# Sheet1.net
KiCad netlist of a schematic drawn in Altium Designer
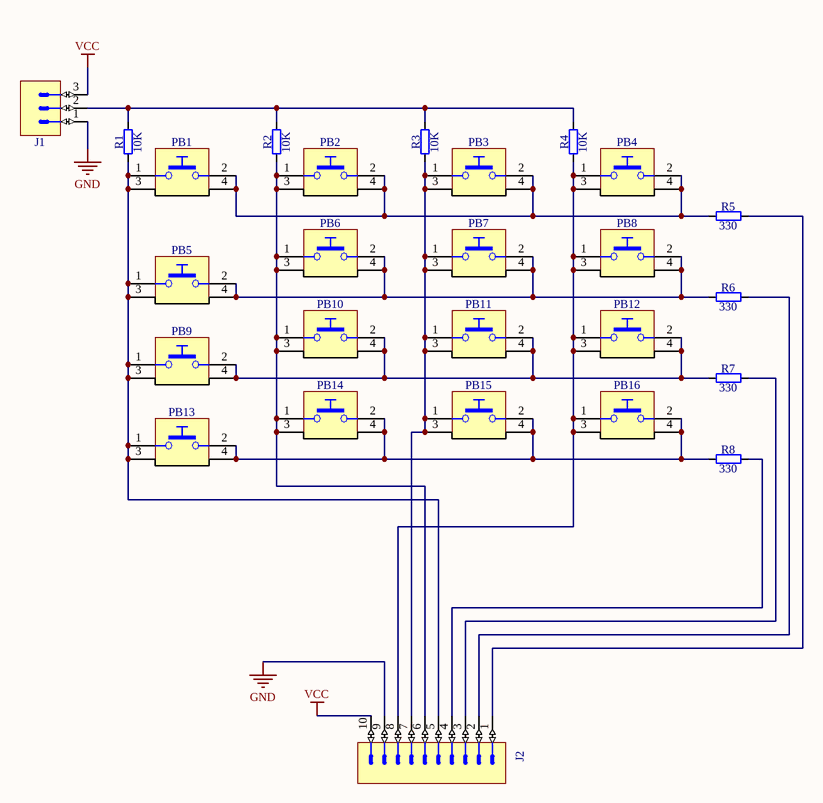
[diagram p0: Sheet1.SchDoc]

(export (version "E")
  (design (tool "Eeschema 10.0.6"))
  (components
    (comp (ref "J1")
      (value "~")
      (footprint "HARWIN_M22-2010305")
      (description "Connector 3 Male")
      (libsource (lib "Schlib1") (part "Connector 3 Male"))
    )
    (comp (ref "J2")
      (value "~")
      (footprint "SIP10")
      (description "Connector 10 Male")
      (libsource (lib "Schlib1") (part "Connector 10 Male"))
    )
    (comp (ref "PB1")
      (value "~")
      (footprint "PB_TYCO_FSM6JSMA")
      (description "Push-Button Switch SPDT")
      (libsource (lib "Schlib1") (part "PB SPST 1NO-2NO 34CASE"))
    )
    (comp (ref "PB2")
      (value "~")
      (footprint "PB_TYCO_FSM6JSMA")
      (description "Push-Button Switch SPDT")
      (libsource (lib "Schlib1") (part "PB SPST 1NO-2NO 34CASE"))
    )
    (comp (ref "PB3")
      (value "~")
      (footprint "PB_TYCO_FSM6JSMA")
      (description "Push-Button Switch SPDT")
      (libsource (lib "Schlib1") (part "PB SPST 1NO-2NO 34CASE"))
    )
    (comp (ref "PB4")
      (value "~")
      (footprint "PB_TYCO_FSM6JSMA")
      (description "Push-Button Switch SPDT")
      (libsource (lib "Schlib1") (part "PB SPST 1NO-2NO 34CASE"))
    )
    (comp (ref "PB5")
      (value "~")
      (footprint "PB_TYCO_FSM6JSMA")
      (description "Push-Button Switch SPDT")
      (libsource (lib "Schlib1") (part "PB SPST 1NO-2NO 34CASE"))
    )
    (comp (ref "PB6")
      (value "~")
      (footprint "PB_TYCO_FSM6JSMA")
      (description "Push-Button Switch SPDT")
      (libsource (lib "Schlib1") (part "PB SPST 1NO-2NO 34CASE"))
    )
    (comp (ref "PB7")
      (value "~")
      (footprint "PB_TYCO_FSM6JSMA")
      (description "Push-Button Switch SPDT")
      (libsource (lib "Schlib1") (part "PB SPST 1NO-2NO 34CASE"))
    )
    (comp (ref "PB8")
      (value "~")
      (footprint "PB_TYCO_FSM6JSMA")
      (description "Push-Button Switch SPDT")
      (libsource (lib "Schlib1") (part "PB SPST 1NO-2NO 34CASE"))
    )
    (comp (ref "PB9")
      (value "~")
      (footprint "PB_TYCO_FSM6JSMA")
      (description "Push-Button Switch SPDT")
      (libsource (lib "Schlib1") (part "PB SPST 1NO-2NO 34CASE"))
    )
    (comp (ref "PB10")
      (value "~")
      (footprint "PB_TYCO_FSM6JSMA")
      (description "Push-Button Switch SPDT")
      (libsource (lib "Schlib1") (part "PB SPST 1NO-2NO 34CASE"))
    )
    (comp (ref "PB11")
      (value "~")
      (footprint "PB_TYCO_FSM6JSMA")
      (description "Push-Button Switch SPDT")
      (libsource (lib "Schlib1") (part "PB SPST 1NO-2NO 34CASE"))
    )
    (comp (ref "PB12")
      (value "~")
      (footprint "PB_TYCO_FSM6JSMA")
      (description "Push-Button Switch SPDT")
      (libsource (lib "Schlib1") (part "PB SPST 1NO-2NO 34CASE"))
    )
    (comp (ref "PB13")
      (value "~")
      (footprint "PB_TYCO_FSM6JSMA")
      (description "Push-Button Switch SPDT")
      (libsource (lib "Schlib1") (part "PB SPST 1NO-2NO 34CASE"))
    )
    (comp (ref "PB14")
      (value "~")
      (footprint "PB_TYCO_FSM6JSMA")
      (description "Push-Button Switch SPDT")
      (libsource (lib "Schlib1") (part "PB SPST 1NO-2NO 34CASE"))
    )
    (comp (ref "PB15")
      (value "~")
      (footprint "PB_TYCO_FSM6JSMA")
      (description "Push-Button Switch SPDT")
      (libsource (lib "Schlib1") (part "PB SPST 1NO-2NO 34CASE"))
    )
    (comp (ref "PB16")
      (value "~")
      (footprint "PB_TYCO_FSM6JSMA")
      (description "Push-Button Switch SPDT")
      (libsource (lib "Schlib1") (part "PB SPST 1NO-2NO 34CASE"))
    )
    (comp (ref "R1")
      (value "10K")
      (footprint "RESC2012X60N")
      (description "Resistor")
      (libsource (lib "Schlib1") (part "Resistor"))
    )
    (comp (ref "R2")
      (value "10K")
      (footprint "RESC2012X60N")
      (description "Resistor")
      (libsource (lib "Schlib1") (part "Resistor"))
    )
    (comp (ref "R3")
      (value "10K")
      (footprint "RESC2012X60N")
      (description "Resistor")
      (libsource (lib "Schlib1") (part "Resistor"))
    )
    (comp (ref "R4")
      (value "10K")
      (footprint "RESC2012X60N")
      (description "Resistor")
      (libsource (lib "Schlib1") (part "Resistor"))
    )
    (comp (ref "R5")
      (value "330")
      (footprint "RESC2012X60N")
      (description "Resistor")
      (libsource (lib "Schlib1") (part "Resistor"))
    )
    (comp (ref "R6")
      (value "330")
      (footprint "RESC2012X60N")
      (description "Resistor")
      (libsource (lib "Schlib1") (part "Resistor"))
    )
    (comp (ref "R7")
      (value "330")
      (footprint "RESC2012X60N")
      (description "Resistor")
      (libsource (lib "Schlib1") (part "Resistor"))
    )
    (comp (ref "R8")
      (value "330")
      (footprint "RESC2012X60N")
      (description "Resistor")
      (libsource (lib "Schlib1") (part "Resistor"))
    )
  )
  (nets
    (net (code "1") (name "GND") (class "Default")
      (node (ref "J1") (pin "1") (pinfunction "1_1") (pintype "bidirectional"))
      (node (ref "J2") (pin "9") (pinfunction "9_9") (pintype "bidirectional"))
    )
    (net (code "2") (name "Net-(J1-Pad2)") (class "Default")
      (node (ref "J1") (pin "2") (pinfunction "2_2") (pintype "bidirectional"))
      (node (ref "R1") (pin "2") (pinfunction "2_2") (pintype "passive"))
      (node (ref "R2") (pin "2") (pinfunction "2_2") (pintype "passive"))
      (node (ref "R3") (pin "2") (pinfunction "2_2") (pintype "passive"))
      (node (ref "R4") (pin "2") (pinfunction "2_2") (pintype "passive"))
    )
    (net (code "3") (name "Net-(J2-Pad1)") (class "Default")
      (node (ref "J2") (pin "1") (pinfunction "1_1") (pintype "bidirectional"))
      (node (ref "R5") (pin "2") (pinfunction "2_2") (pintype "passive"))
    )
    (net (code "4") (name "Net-(J2-Pad2)") (class "Default")
      (node (ref "J2") (pin "2") (pinfunction "2_2") (pintype "bidirectional"))
      (node (ref "R6") (pin "2") (pinfunction "2_2") (pintype "passive"))
    )
    (net (code "5") (name "Net-(J2-Pad3)") (class "Default")
      (node (ref "J2") (pin "3") (pinfunction "3_3") (pintype "bidirectional"))
      (node (ref "R7") (pin "2") (pinfunction "2_2") (pintype "passive"))
    )
    (net (code "6") (name "Net-(J2-Pad4)") (class "Default")
      (node (ref "J2") (pin "4") (pinfunction "4_4") (pintype "bidirectional"))
      (node (ref "R8") (pin "2") (pinfunction "2_2") (pintype "passive"))
    )
    (net (code "7") (name "Net-(J2-Pad5)") (class "Default")
      (node (ref "J2") (pin "5") (pinfunction "5_5") (pintype "bidirectional"))
      (node (ref "PB1") (pin "1") (pinfunction "1_1") (pintype "passive"))
      (node (ref "PB1") (pin "3") (pinfunction "3_3") (pintype "passive"))
      (node (ref "PB13") (pin "1") (pinfunction "1_1") (pintype "passive"))
      (node (ref "PB13") (pin "3") (pinfunction "3_3") (pintype "passive"))
      (node (ref "PB5") (pin "1") (pinfunction "1_1") (pintype "passive"))
      (node (ref "PB5") (pin "3") (pinfunction "3_3") (pintype "passive"))
      (node (ref "PB9") (pin "1") (pinfunction "1_1") (pintype "passive"))
      (node (ref "PB9") (pin "3") (pinfunction "3_3") (pintype "passive"))
      (node (ref "R1") (pin "1") (pinfunction "1_1") (pintype "passive"))
    )
    (net (code "8") (name "Net-(J2-Pad6)") (class "Default")
      (node (ref "J2") (pin "6") (pinfunction "6_6") (pintype "bidirectional"))
      (node (ref "PB10") (pin "1") (pinfunction "1_1") (pintype "passive"))
      (node (ref "PB10") (pin "3") (pinfunction "3_3") (pintype "passive"))
      (node (ref "PB14") (pin "1") (pinfunction "1_1") (pintype "passive"))
      (node (ref "PB14") (pin "3") (pinfunction "3_3") (pintype "passive"))
      (node (ref "PB2") (pin "1") (pinfunction "1_1") (pintype "passive"))
      (node (ref "PB2") (pin "3") (pinfunction "3_3") (pintype "passive"))
      (node (ref "PB6") (pin "1") (pinfunction "1_1") (pintype "passive"))
      (node (ref "PB6") (pin "3") (pinfunction "3_3") (pintype "passive"))
      (node (ref "R2") (pin "1") (pinfunction "1_1") (pintype "passive"))
    )
    (net (code "9") (name "Net-(J2-Pad7)") (class "Default")
      (node (ref "J2") (pin "7") (pinfunction "7_7") (pintype "bidirectional"))
      (node (ref "PB11") (pin "1") (pinfunction "1_1") (pintype "passive"))
      (node (ref "PB11") (pin "3") (pinfunction "3_3") (pintype "passive"))
      (node (ref "PB15") (pin "1") (pinfunction "1_1") (pintype "passive"))
      (node (ref "PB15") (pin "3") (pinfunction "3_3") (pintype "passive"))
      (node (ref "PB3") (pin "1") (pinfunction "1_1") (pintype "passive"))
      (node (ref "PB3") (pin "3") (pinfunction "3_3") (pintype "passive"))
      (node (ref "PB7") (pin "1") (pinfunction "1_1") (pintype "passive"))
      (node (ref "PB7") (pin "3") (pinfunction "3_3") (pintype "passive"))
      (node (ref "R3") (pin "1") (pinfunction "1_1") (pintype "passive"))
    )
    (net (code "10") (name "Net-(J2-Pad8)") (class "Default")
      (node (ref "J2") (pin "8") (pinfunction "8_8") (pintype "bidirectional"))
      (node (ref "PB12") (pin "1") (pinfunction "1_1") (pintype "passive"))
      (node (ref "PB12") (pin "3") (pinfunction "3_3") (pintype "passive"))
      (node (ref "PB16") (pin "1") (pinfunction "1_1") (pintype "passive"))
      (node (ref "PB16") (pin "3") (pinfunction "3_3") (pintype "passive"))
      (node (ref "PB4") (pin "1") (pinfunction "1_1") (pintype "passive"))
      (node (ref "PB4") (pin "3") (pinfunction "3_3") (pintype "passive"))
      (node (ref "PB8") (pin "1") (pinfunction "1_1") (pintype "passive"))
      (node (ref "PB8") (pin "3") (pinfunction "3_3") (pintype "passive"))
      (node (ref "R4") (pin "1") (pinfunction "1_1") (pintype "passive"))
    )
    (net (code "11") (name "Net-(PB1-Pad2)") (class "Default")
      (node (ref "PB1") (pin "2") (pinfunction "2_2") (pintype "passive"))
      (node (ref "PB1") (pin "4") (pinfunction "4_4") (pintype "passive"))
      (node (ref "PB2") (pin "2") (pinfunction "2_2") (pintype "passive"))
      (node (ref "PB2") (pin "4") (pinfunction "4_4") (pintype "passive"))
      (node (ref "PB3") (pin "2") (pinfunction "2_2") (pintype "passive"))
      (node (ref "PB3") (pin "4") (pinfunction "4_4") (pintype "passive"))
      (node (ref "PB4") (pin "2") (pinfunction "2_2") (pintype "passive"))
      (node (ref "PB4") (pin "4") (pinfunction "4_4") (pintype "passive"))
      (node (ref "R5") (pin "1") (pinfunction "1_1") (pintype "passive"))
    )
    (net (code "12") (name "Net-(PB5-Pad2)") (class "Default")
      (node (ref "PB5") (pin "2") (pinfunction "2_2") (pintype "passive"))
      (node (ref "PB5") (pin "4") (pinfunction "4_4") (pintype "passive"))
      (node (ref "PB6") (pin "2") (pinfunction "2_2") (pintype "passive"))
      (node (ref "PB6") (pin "4") (pinfunction "4_4") (pintype "passive"))
      (node (ref "PB7") (pin "2") (pinfunction "2_2") (pintype "passive"))
      (node (ref "PB7") (pin "4") (pinfunction "4_4") (pintype "passive"))
      (node (ref "PB8") (pin "2") (pinfunction "2_2") (pintype "passive"))
      (node (ref "PB8") (pin "4") (pinfunction "4_4") (pintype "passive"))
      (node (ref "R6") (pin "1") (pinfunction "1_1") (pintype "passive"))
    )
    (net (code "13") (name "Net-(PB10-Pad2)") (class "Default")
      (node (ref "PB10") (pin "2") (pinfunction "2_2") (pintype "passive"))
      (node (ref "PB10") (pin "4") (pinfunction "4_4") (pintype "passive"))
      (node (ref "PB11") (pin "2") (pinfunction "2_2") (pintype "passive"))
      (node (ref "PB11") (pin "4") (pinfunction "4_4") (pintype "passive"))
      (node (ref "PB12") (pin "2") (pinfunction "2_2") (pintype "passive"))
      (node (ref "PB12") (pin "4") (pinfunction "4_4") (pintype "passive"))
      (node (ref "PB9") (pin "2") (pinfunction "2_2") (pintype "passive"))
      (node (ref "PB9") (pin "4") (pinfunction "4_4") (pintype "passive"))
      (node (ref "R7") (pin "1") (pinfunction "1_1") (pintype "passive"))
    )
    (net (code "14") (name "Net-(PB13-Pad2)") (class "Default")
      (node (ref "PB13") (pin "2") (pinfunction "2_2") (pintype "passive"))
      (node (ref "PB13") (pin "4") (pinfunction "4_4") (pintype "passive"))
      (node (ref "PB14") (pin "2") (pinfunction "2_2") (pintype "passive"))
      (node (ref "PB14") (pin "4") (pinfunction "4_4") (pintype "passive"))
      (node (ref "PB15") (pin "2") (pinfunction "2_2") (pintype "passive"))
      (node (ref "PB15") (pin "4") (pinfunction "4_4") (pintype "passive"))
      (node (ref "PB16") (pin "2") (pinfunction "2_2") (pintype "passive"))
      (node (ref "PB16") (pin "4") (pinfunction "4_4") (pintype "passive"))
      (node (ref "R8") (pin "1") (pinfunction "1_1") (pintype "passive"))
    )
    (net (code "15") (name "VCC") (class "Default")
      (node (ref "J1") (pin "3") (pinfunction "3_3") (pintype "bidirectional"))
      (node (ref "J2") (pin "10") (pinfunction "10_10") (pintype "bidirectional"))
    )
  )
)
